# STM32F103VE.net
KiCad netlist of a schematic drawn in Altium Designer
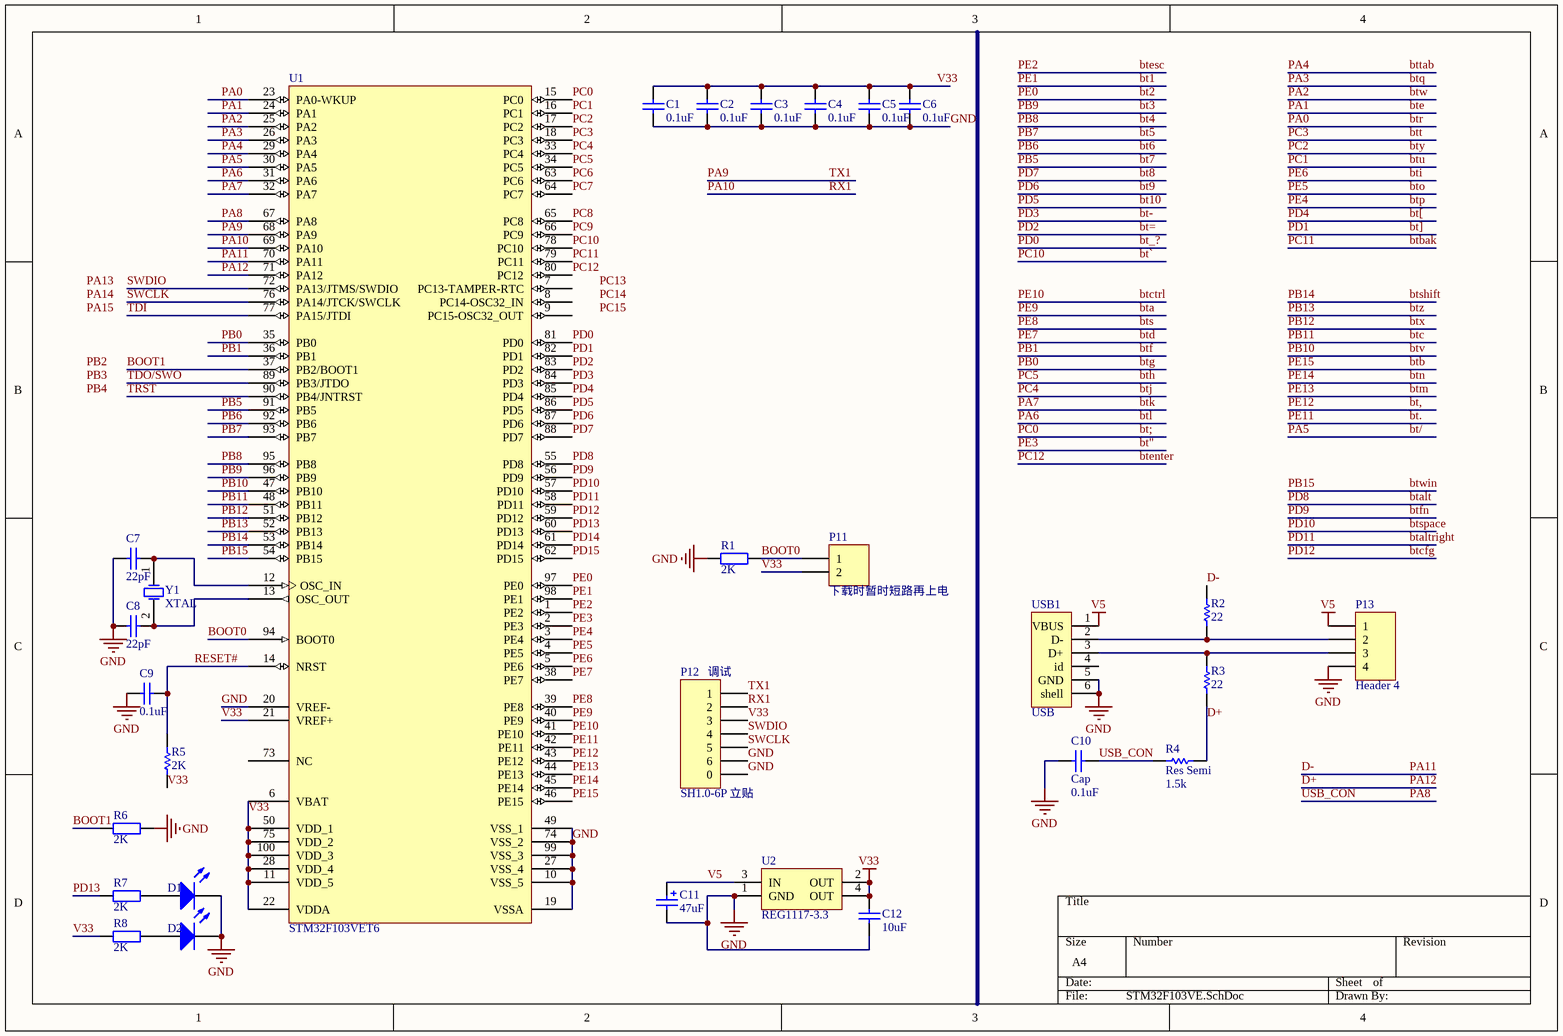
[diagram p0: STM32F103VE.SchDoc]

(export (version "E")
  (design (tool "Eeschema 10.0.6"))
  (components
    (comp (ref "C1")
      (value "0.1uF")
      (footprint "CAP0805(2512)")
      (description "Capacitor")
      (fields (field (name "Comment") "Cap") (field (name "PUBLISHER") "Altium Limited"))
      (libsource (lib "Miscellaneous Devices") (part "Cap"))
    )
    (comp (ref "C2")
      (value "0.1uF")
      (footprint "CAP0805(2512)")
      (description "Capacitor")
      (fields (field (name "Comment") "Cap") (field (name "PUBLISHER") "Altium Limited"))
      (libsource (lib "Miscellaneous Devices") (part "Cap"))
    )
    (comp (ref "C3")
      (value "0.1uF")
      (footprint "CAP0805(2512)")
      (description "Capacitor")
      (fields (field (name "Comment") "Cap") (field (name "PUBLISHER") "Altium Limited"))
      (libsource (lib "Miscellaneous Devices") (part "Cap"))
    )
    (comp (ref "C4")
      (value "0.1uF")
      (footprint "CAP0805(2512)")
      (description "Capacitor")
      (fields (field (name "Comment") "Cap") (field (name "PUBLISHER") "Altium Limited"))
      (libsource (lib "Miscellaneous Devices") (part "Cap"))
    )
    (comp (ref "C5")
      (value "0.1uF")
      (footprint "CAP0805(2512)")
      (description "Capacitor")
      (fields (field (name "Comment") "Cap") (field (name "PUBLISHER") "Altium Limited"))
      (libsource (lib "Miscellaneous Devices") (part "Cap"))
    )
    (comp (ref "C6")
      (value "0.1uF")
      (footprint "CAP0805(2512)")
      (description "Capacitor")
      (fields (field (name "Comment") "Cap") (field (name "PUBLISHER") "Altium Limited"))
      (libsource (lib "Miscellaneous Devices") (part "Cap"))
    )
    (comp (ref "C7")
      (value "22pF")
      (footprint "CAP0805(2512)")
      (description "Capacitor")
      (fields (field (name "Comment") "Cap") (field (name "PUBLISHER") "Altium Limited"))
      (libsource (lib "Miscellaneous Devices") (part "Cap"))
    )
    (comp (ref "C8")
      (value "22pF")
      (footprint "CAP0805(2512)")
      (description "Capacitor")
      (fields (field (name "Comment") "Cap") (field (name "PUBLISHER") "Altium Limited"))
      (libsource (lib "Miscellaneous Devices") (part "Cap"))
    )
    (comp (ref "C9")
      (value "0.1uF")
      (footprint "CAP0805(2512)")
      (description "Capacitor")
      (fields (field (name "Comment") "Cap") (field (name "PUBLISHER") "Altium Limited"))
      (libsource (lib "Miscellaneous Devices") (part "Cap"))
    )
    (comp (ref "C10")
      (value "Cap")
      (footprint "CAP0805(2512)")
      (description "Capacitor")
      (fields (field (name "ALTIUM_VALUE") "0.1uF") (field (name "PUBLISHER") "Altium Limited"))
      (libsource (lib "Miscellaneous Devices") (part "Cap"))
    )
    (comp (ref "C11")
      (value "47uF")
      (footprint "CAP0805(2512)")
      (description "Polarized Capacitor (Axial)")
      (fields (field (name "Comment") "Cap Pol2") (field (name "PUBLISHER") "Altium Limited"))
      (libsource (lib "Miscellaneous Devices") (part "Cap Pol2"))
    )
    (comp (ref "C12")
      (value "10uF")
      (footprint "CAP0805(2512)")
      (description "Capacitor")
      (fields (field (name "Comment") "Cap") (field (name "PUBLISHER") "Altium Limited"))
      (libsource (lib "Miscellaneous Devices") (part "Cap"))
    )
    (comp (ref "D1")
      (value "LED0")
      (footprint "DIODE_100mil")
      (description "Typical INFRARED GaAs LED")
      (fields (field (name "PUBLISHER") "Altium Limited"))
      (libsource (lib "Miscellaneous Devices") (part "LED0"))
    )
    (comp (ref "D2")
      (value "LED0")
      (footprint "DIODE_100mil")
      (description "Typical INFRARED GaAs LED")
      (fields (field (name "PUBLISHER") "Altium Limited"))
      (libsource (lib "Miscellaneous Devices") (part "LED0"))
    )
    (comp (ref "P11")
      (value "下载时暂时短路再上电")
      (footprint "HDR1X2")
      (description "Header, 2-Pin")
      (fields (field (name "PUBLISHER") "Altium Limited"))
      (libsource (lib "Miscellaneous Connectors") (part "Header 2"))
    )
    (comp (ref "P12")
      (value "SH1.0-6P 立贴")
      (footprint "SH1.0-6P立")
      (description "Header, 7-Pin")
      (fields (field (name "PUBLISHER") "Altium Limited"))
      (libsource (lib "Miscellaneous Connectors") (part "Header 7"))
    )
    (comp (ref "P13")
      (value "Header 4")
      (footprint "HDR1X4")
      (description "Header, 4-Pin")
      (fields (field (name "PUBLISHER") "Altium Limited"))
      (libsource (lib "Miscellaneous Connectors") (part "Header 4"))
    )
    (comp (ref "R1")
      (value "2K")
      (footprint "RES0805(2012M)")
      (description "Resistor")
      (fields (field (name "Comment") "Res2") (field (name "PUBLISHER") "Altium Limited"))
      (libsource (lib "Miscellaneous Devices") (part "Res2"))
    )
    (comp (ref "R2")
      (value "22")
      (footprint "RES0805(2012M)")
      (description "Semiconductor Resistor")
      (fields (field (name "Comment") "Res Semi") (field (name "PUBLISHER") "Altium Limited"))
      (libsource (lib "Miscellaneous Devices") (part "Res Semi"))
    )
    (comp (ref "R3")
      (value "22")
      (footprint "RES0805(2012M)")
      (description "Semiconductor Resistor")
      (fields (field (name "Comment") "Res Semi") (field (name "PUBLISHER") "Altium Limited"))
      (libsource (lib "Miscellaneous Devices") (part "Res Semi"))
    )
    (comp (ref "R4")
      (value "Res Semi")
      (footprint "RES0805(2012M)")
      (description "Semiconductor Resistor")
      (fields (field (name "ALTIUM_VALUE") "1.5k") (field (name "PUBLISHER") "Altium Limited"))
      (libsource (lib "Miscellaneous Devices") (part "Res Semi"))
    )
    (comp (ref "R5")
      (value "2K")
      (footprint "RES0805(2012M)")
      (description "Semiconductor Resistor")
      (fields (field (name "Comment") "Res Semi") (field (name "PUBLISHER") "Altium Limited"))
      (libsource (lib "Miscellaneous Devices") (part "Res Semi"))
    )
    (comp (ref "R6")
      (value "2K")
      (footprint "RES0805(2012M)")
      (description "Resistor")
      (fields (field (name "Comment") "Res2") (field (name "PUBLISHER") "Altium Limited"))
      (libsource (lib "Miscellaneous Devices") (part "Res2"))
    )
    (comp (ref "R7")
      (value "2K")
      (footprint "RES0805(2012M)")
      (description "Resistor")
      (fields (field (name "Comment") "Res2") (field (name "PUBLISHER") "Altium Limited"))
      (libsource (lib "") (part "Res2_1"))
    )
    (comp (ref "R8")
      (value "2K")
      (footprint "RES0805(2012M)")
      (description "Resistor")
      (fields (field (name "Comment") "Res2") (field (name "PUBLISHER") "Altium Limited"))
      (libsource (lib "") (part "Res2_1"))
    )
    (comp (ref "U1")
      (value "STM32F103VET6")
      (footprint "LQFP-100")
      (description "STM32 ARM-based 32-bit MCU with 64 Kbytes Flash, 100-pin LQFP, Industrial Temperature")
      (fields (field (name "PUBLISHER") "Altium Limited"))
      (libsource (lib "ST Microcontroller 32-Bit STM32") (part "STM32F103VBT6"))
    )
    (comp (ref "U2")
      (value "REG1117-3.3")
      (footprint "ZZ311")
      (description "800mA and 1A Low Dropout Positive Regulator 2.85V, 3.3V, 5V, and Adjustable")
      (fields (field (name "PUBLISHER") "Altium Limited"))
      (libsource (lib "power") (part "REG1117-3.3"))
    )
    (comp (ref "USB1") (value "USB") (footprint "MICRO-USB") (libsource (lib "*") (part "USB")))
    (comp (ref "Y1")
      (value "XTAL")
      (footprint "XTAL_0.4")
      (description "Crystal Oscillator")
      (fields (field (name "PUBLISHER") "Altium Limited"))
      (libsource (lib "Miscellaneous Devices") (part "XTAL"))
    )
  )
  (nets
    (net (code "1") (name "/BOOT0") (class "Default")
      (node (ref "P11") (pin "1") (pinfunction "1_1") (pintype "passive"))
      (node (ref "R1") (pin "1") (pinfunction "1_1") (pintype "passive"))
      (node (ref "U1") (pin "94") (pinfunction "BOOT0_94") (pintype "input"))
    )
    (net (code "2") (name "/BOOT1") (class "Default")
      (node (ref "R6") (pin "2") (pinfunction "2_2") (pintype "passive"))
      (node (ref "U1") (pin "37") (pinfunction "PB2/BOOT1_37") (pintype "bidirectional"))
    )
    (net (code "3") (name "/D+") (class "Default")
      (node (ref "R3") (pin "2") (pinfunction "2_2") (pintype "passive"))
      (node (ref "R4") (pin "2") (pinfunction "2_2") (pintype "passive"))
      (node (ref "U1") (pin "71") (pinfunction "PA12_71") (pintype "bidirectional"))
    )
    (net (code "4") (name "/D-") (class "Default")
      (node (ref "R2") (pin "2") (pinfunction "2_2") (pintype "passive"))
      (node (ref "U1") (pin "70") (pinfunction "PA11_70") (pintype "bidirectional"))
    )
    (net (code "5") (name "/PA0") (class "Default")
      (node (ref "U1") (pin "23") (pinfunction "PA0-WKUP_23") (pintype "bidirectional"))
    )
    (net (code "6") (name "/PA1") (class "Default")
      (node (ref "U1") (pin "24") (pinfunction "PA1_24") (pintype "bidirectional"))
    )
    (net (code "7") (name "/PA2") (class "Default")
      (node (ref "U1") (pin "25") (pinfunction "PA2_25") (pintype "bidirectional"))
    )
    (net (code "8") (name "/PA3") (class "Default")
      (node (ref "U1") (pin "26") (pinfunction "PA3_26") (pintype "bidirectional"))
    )
    (net (code "9") (name "/PA4") (class "Default")
      (node (ref "U1") (pin "29") (pinfunction "PA4_29") (pintype "bidirectional"))
    )
    (net (code "10") (name "/PA5") (class "Default")
      (node (ref "U1") (pin "30") (pinfunction "PA5_30") (pintype "bidirectional"))
    )
    (net (code "11") (name "/PA6") (class "Default")
      (node (ref "U1") (pin "31") (pinfunction "PA6_31") (pintype "bidirectional"))
    )
    (net (code "12") (name "/PA7") (class "Default")
      (node (ref "U1") (pin "32") (pinfunction "PA7_32") (pintype "bidirectional"))
    )
    (net (code "13") (name "/PA8") (class "Default")
      (node (ref "C10") (pin "1") (pinfunction "1_1") (pintype "passive"))
      (node (ref "R4") (pin "1") (pinfunction "1_1") (pintype "passive"))
      (node (ref "U1") (pin "67") (pinfunction "PA8_67") (pintype "bidirectional"))
    )
    (net (code "14") (name "/PA9") (class "Default")
      (node (ref "P12") (pin "1") (pinfunction "1_1") (pintype "passive"))
      (node (ref "U1") (pin "68") (pinfunction "PA9_68") (pintype "bidirectional"))
    )
    (net (code "15") (name "/PA10") (class "Default")
      (node (ref "P12") (pin "2") (pinfunction "2_2") (pintype "passive"))
      (node (ref "U1") (pin "69") (pinfunction "PA10_69") (pintype "bidirectional"))
    )
    (net (code "19") (name "/PB0") (class "Default")
      (node (ref "U1") (pin "35") (pinfunction "PB0_35") (pintype "bidirectional"))
    )
    (net (code "20") (name "/PB1") (class "Default")
      (node (ref "U1") (pin "36") (pinfunction "PB1_36") (pintype "bidirectional"))
    )
    (net (code "24") (name "/PB5") (class "Default")
      (node (ref "U1") (pin "91") (pinfunction "PB5_91") (pintype "bidirectional"))
    )
    (net (code "25") (name "/PB6") (class "Default")
      (node (ref "U1") (pin "92") (pinfunction "PB6_92") (pintype "bidirectional"))
    )
    (net (code "26") (name "/PB7") (class "Default")
      (node (ref "U1") (pin "93") (pinfunction "PB7_93") (pintype "bidirectional"))
    )
    (net (code "27") (name "/PB8") (class "Default")
      (node (ref "U1") (pin "95") (pinfunction "PB8_95") (pintype "bidirectional"))
    )
    (net (code "28") (name "/PB9") (class "Default")
      (node (ref "U1") (pin "96") (pinfunction "PB9_96") (pintype "bidirectional"))
    )
    (net (code "29") (name "/PB10") (class "Default")
      (node (ref "U1") (pin "47") (pinfunction "PB10_47") (pintype "bidirectional"))
    )
    (net (code "30") (name "/PB11") (class "Default")
      (node (ref "U1") (pin "48") (pinfunction "PB11_48") (pintype "bidirectional"))
    )
    (net (code "31") (name "/PB12") (class "Default")
      (node (ref "U1") (pin "51") (pinfunction "PB12_51") (pintype "bidirectional"))
    )
    (net (code "32") (name "/PB13") (class "Default")
      (node (ref "U1") (pin "52") (pinfunction "PB13_52") (pintype "bidirectional"))
    )
    (net (code "33") (name "/PB14") (class "Default")
      (node (ref "U1") (pin "53") (pinfunction "PB14_53") (pintype "bidirectional"))
    )
    (net (code "34") (name "/PB15") (class "Default")
      (node (ref "U1") (pin "54") (pinfunction "PB15_54") (pintype "bidirectional"))
    )
    (net (code "35") (name "/PC0") (class "Default")
      (node (ref "U1") (pin "15") (pinfunction "PC0_15") (pintype "bidirectional"))
    )
    (net (code "36") (name "/PC1") (class "Default")
      (node (ref "U1") (pin "16") (pinfunction "PC1_16") (pintype "bidirectional"))
    )
    (net (code "37") (name "/PC2") (class "Default")
      (node (ref "U1") (pin "17") (pinfunction "PC2_17") (pintype "bidirectional"))
    )
    (net (code "38") (name "/PC3") (class "Default")
      (node (ref "U1") (pin "18") (pinfunction "PC3_18") (pintype "bidirectional"))
    )
    (net (code "39") (name "/PC4") (class "Default")
      (node (ref "U1") (pin "33") (pinfunction "PC4_33") (pintype "bidirectional"))
    )
    (net (code "40") (name "/PC5") (class "Default")
      (node (ref "U1") (pin "34") (pinfunction "PC5_34") (pintype "bidirectional"))
    )
    (net (code "41") (name "/PC6") (class "Default")
      (node (ref "U1") (pin "63") (pinfunction "PC6_63") (pintype "bidirectional"))
    )
    (net (code "42") (name "/PC7") (class "Default")
      (node (ref "U1") (pin "64") (pinfunction "PC7_64") (pintype "bidirectional"))
    )
    (net (code "43") (name "/PC8") (class "Default")
      (node (ref "U1") (pin "65") (pinfunction "PC8_65") (pintype "bidirectional"))
    )
    (net (code "44") (name "/PC9") (class "Default")
      (node (ref "U1") (pin "66") (pinfunction "PC9_66") (pintype "bidirectional"))
    )
    (net (code "45") (name "/PC10") (class "Default")
      (node (ref "U1") (pin "78") (pinfunction "PC10_78") (pintype "bidirectional"))
    )
    (net (code "46") (name "/PC11") (class "Default")
      (node (ref "U1") (pin "79") (pinfunction "PC11_79") (pintype "bidirectional"))
    )
    (net (code "47") (name "/PC12") (class "Default")
      (node (ref "U1") (pin "80") (pinfunction "PC12_80") (pintype "bidirectional"))
    )
    (net (code "51") (name "/PD0") (class "Default")
      (node (ref "U1") (pin "81") (pinfunction "PD0_81") (pintype "bidirectional"))
    )
    (net (code "52") (name "/PD1") (class "Default")
      (node (ref "U1") (pin "82") (pinfunction "PD1_82") (pintype "bidirectional"))
    )
    (net (code "53") (name "/PD2") (class "Default")
      (node (ref "U1") (pin "83") (pinfunction "PD2_83") (pintype "bidirectional"))
    )
    (net (code "54") (name "/PD3") (class "Default")
      (node (ref "U1") (pin "84") (pinfunction "PD3_84") (pintype "bidirectional"))
    )
    (net (code "55") (name "/PD4") (class "Default")
      (node (ref "U1") (pin "85") (pinfunction "PD4_85") (pintype "bidirectional"))
    )
    (net (code "56") (name "/PD5") (class "Default")
      (node (ref "U1") (pin "86") (pinfunction "PD5_86") (pintype "bidirectional"))
    )
    (net (code "57") (name "/PD6") (class "Default")
      (node (ref "U1") (pin "87") (pinfunction "PD6_87") (pintype "bidirectional"))
    )
    (net (code "58") (name "/PD7") (class "Default")
      (node (ref "U1") (pin "88") (pinfunction "PD7_88") (pintype "bidirectional"))
    )
    (net (code "59") (name "/PD8") (class "Default")
      (node (ref "U1") (pin "55") (pinfunction "PD8_55") (pintype "bidirectional"))
    )
    (net (code "60") (name "/PD9") (class "Default")
      (node (ref "U1") (pin "56") (pinfunction "PD9_56") (pintype "bidirectional"))
    )
    (net (code "61") (name "/PD10") (class "Default")
      (node (ref "U1") (pin "57") (pinfunction "PD10_57") (pintype "bidirectional"))
    )
    (net (code "62") (name "/PD11") (class "Default")
      (node (ref "U1") (pin "58") (pinfunction "PD11_58") (pintype "bidirectional"))
    )
    (net (code "63") (name "/PD12") (class "Default")
      (node (ref "U1") (pin "59") (pinfunction "PD12_59") (pintype "bidirectional"))
    )
    (net (code "64") (name "/PD13") (class "Default")
      (node (ref "R7") (pin "1") (pinfunction "1_1") (pintype "passive"))
      (node (ref "U1") (pin "60") (pinfunction "PD13_60") (pintype "bidirectional"))
    )
    (net (code "65") (name "/PD14") (class "Default")
      (node (ref "U1") (pin "61") (pinfunction "PD14_61") (pintype "bidirectional"))
    )
    (net (code "66") (name "/PD15") (class "Default")
      (node (ref "U1") (pin "62") (pinfunction "PD15_62") (pintype "bidirectional"))
    )
    (net (code "67") (name "/PE0") (class "Default")
      (node (ref "U1") (pin "97") (pinfunction "PE0_97") (pintype "bidirectional"))
    )
    (net (code "68") (name "/PE1") (class "Default")
      (node (ref "U1") (pin "98") (pinfunction "PE1_98") (pintype "bidirectional"))
    )
    (net (code "69") (name "/PE2") (class "Default")
      (node (ref "U1") (pin "1") (pinfunction "PE2_1") (pintype "bidirectional"))
    )
    (net (code "70") (name "/PE3") (class "Default")
      (node (ref "U1") (pin "2") (pinfunction "PE3_2") (pintype "bidirectional"))
    )
    (net (code "71") (name "/PE4") (class "Default")
      (node (ref "U1") (pin "3") (pinfunction "PE4_3") (pintype "bidirectional"))
    )
    (net (code "72") (name "/PE5") (class "Default")
      (node (ref "U1") (pin "4") (pinfunction "PE5_4") (pintype "bidirectional"))
    )
    (net (code "73") (name "/PE6") (class "Default")
      (node (ref "U1") (pin "5") (pinfunction "PE6_5") (pintype "bidirectional"))
    )
    (net (code "74") (name "/PE7") (class "Default")
      (node (ref "U1") (pin "38") (pinfunction "PE7_38") (pintype "bidirectional"))
    )
    (net (code "75") (name "/PE8") (class "Default")
      (node (ref "U1") (pin "39") (pinfunction "PE8_39") (pintype "bidirectional"))
    )
    (net (code "76") (name "/PE9") (class "Default")
      (node (ref "U1") (pin "40") (pinfunction "PE9_40") (pintype "bidirectional"))
    )
    (net (code "77") (name "/PE10") (class "Default")
      (node (ref "U1") (pin "41") (pinfunction "PE10_41") (pintype "bidirectional"))
    )
    (net (code "78") (name "/PE11") (class "Default")
      (node (ref "U1") (pin "42") (pinfunction "PE11_42") (pintype "bidirectional"))
    )
    (net (code "79") (name "/PE12") (class "Default")
      (node (ref "U1") (pin "43") (pinfunction "PE12_43") (pintype "bidirectional"))
    )
    (net (code "80") (name "/PE13") (class "Default")
      (node (ref "U1") (pin "44") (pinfunction "PE13_44") (pintype "bidirectional"))
    )
    (net (code "81") (name "/PE14") (class "Default")
      (node (ref "U1") (pin "45") (pinfunction "PE14_45") (pintype "bidirectional"))
    )
    (net (code "82") (name "/PE15") (class "Default")
      (node (ref "U1") (pin "46") (pinfunction "PE15_46") (pintype "bidirectional"))
    )
    (net (code "83") (name "/RESET#") (class "Default")
      (node (ref "C9") (pin "1") (pinfunction "1_1") (pintype "passive"))
      (node (ref "R5") (pin "2") (pinfunction "2_2") (pintype "passive"))
      (node (ref "U1") (pin "14") (pinfunction "NRST_14") (pintype "bidirectional"))
    )
    (net (code "84") (name "/SWCLK") (class "Default")
      (node (ref "P12") (pin "5") (pinfunction "5_5") (pintype "passive"))
      (node (ref "U1") (pin "76") (pinfunction "PA14/JTCK/SWCLK_76") (pintype "bidirectional"))
    )
    (net (code "85") (name "/SWDIO") (class "Default")
      (node (ref "P12") (pin "4") (pinfunction "4_4") (pintype "passive"))
      (node (ref "U1") (pin "72") (pinfunction "PA13/JTMS/SWDIO_72") (pintype "bidirectional"))
    )
    (net (code "86") (name "/TDI") (class "Default")
      (node (ref "U1") (pin "77") (pinfunction "PA15/JTDI_77") (pintype "bidirectional"))
    )
    (net (code "87") (name "/TDO{slash}SWO") (class "Default")
      (node (ref "U1") (pin "89") (pinfunction "PB3/JTDO_89") (pintype "bidirectional"))
    )
    (net (code "88") (name "/TRST") (class "Default")
      (node (ref "U1") (pin "90") (pinfunction "PB4/JNTRST_90") (pintype "bidirectional"))
    )
    (net (code "89") (name "GND") (class "Default")
      (node (ref "C1") (pin "1") (pinfunction "1_1") (pintype "passive"))
      (node (ref "C10") (pin "2") (pinfunction "2_2") (pintype "passive"))
      (node (ref "C11") (pin "2") (pinfunction "2_2") (pintype "passive"))
      (node (ref "C12") (pin "1") (pinfunction "1_1") (pintype "passive"))
      (node (ref "C2") (pin "1") (pinfunction "1_1") (pintype "passive"))
      (node (ref "C3") (pin "1") (pinfunction "1_1") (pintype "passive"))
      (node (ref "C4") (pin "1") (pinfunction "1_1") (pintype "passive"))
      (node (ref "C5") (pin "1") (pinfunction "1_1") (pintype "passive"))
      (node (ref "C6") (pin "1") (pinfunction "1_1") (pintype "passive"))
      (node (ref "C7") (pin "1") (pinfunction "1_1") (pintype "passive"))
      (node (ref "C8") (pin "1") (pinfunction "1_1") (pintype "passive"))
      (node (ref "C9") (pin "2") (pinfunction "2_2") (pintype "passive"))
      (node (ref "D1") (pin "2") (pinfunction "K_2") (pintype "passive"))
      (node (ref "D2") (pin "2") (pinfunction "K_2") (pintype "passive"))
      (node (ref "P12") (pin "0") (pinfunction "0_0") (pintype "passive"))
      (node (ref "P12") (pin "6") (pinfunction "6_6") (pintype "passive"))
      (node (ref "P13") (pin "4") (pinfunction "4_4") (pintype "passive"))
      (node (ref "R1") (pin "2") (pinfunction "2_2") (pintype "passive"))
      (node (ref "R6") (pin "1") (pinfunction "1_1") (pintype "passive"))
      (node (ref "U1") (pin "10") (pinfunction "VSS_5_10") (pintype "power_in"))
      (node (ref "U1") (pin "19") (pinfunction "VSSA_19") (pintype "power_in"))
      (node (ref "U1") (pin "20") (pinfunction "VREF-_20") (pintype "power_in"))
      (node (ref "U1") (pin "27") (pinfunction "VSS_4_27") (pintype "power_in"))
      (node (ref "U1") (pin "49") (pinfunction "VSS_1_49") (pintype "power_in"))
      (node (ref "U1") (pin "74") (pinfunction "VSS_2_74") (pintype "power_in"))
      (node (ref "U1") (pin "99") (pinfunction "VSS_3_99") (pintype "power_in"))
      (node (ref "U2") (pin "1") (pinfunction "GND_1") (pintype "power_in"))
      (node (ref "USB1") (pin "5") (pinfunction "GND_5") (pintype "passive"))
      (node (ref "USB1") (pin "6") (pinfunction "shell_6") (pintype "passive"))
    )
    (net (code "90") (name "Net-(D1-A)") (class "Default")
      (node (ref "D1") (pin "1") (pinfunction "A_1") (pintype "passive"))
      (node (ref "R7") (pin "2") (pinfunction "2_2") (pintype "passive"))
    )
    (net (code "91") (name "Net-(D2-A)") (class "Default")
      (node (ref "D2") (pin "1") (pinfunction "A_1") (pintype "passive"))
      (node (ref "R8") (pin "2") (pinfunction "2_2") (pintype "passive"))
    )
    (net (code "92") (name "Net-(U1-OSC_IN)") (class "Default")
      (node (ref "C7") (pin "2") (pinfunction "2_2") (pintype "passive"))
      (node (ref "U1") (pin "12") (pinfunction "OSC_IN_12") (pintype "input"))
      (node (ref "Y1") (pin "1") (pinfunction "OSC1_1") (pintype "passive"))
    )
    (net (code "93") (name "Net-(U1-OSC_OUT)") (class "Default")
      (node (ref "C8") (pin "2") (pinfunction "2_2") (pintype "passive"))
      (node (ref "U1") (pin "13") (pinfunction "OSC_OUT_13") (pintype "output"))
      (node (ref "Y1") (pin "2") (pinfunction "OSC2_2") (pintype "passive"))
    )
    (net (code "94") (name "Net-(USB1-D+)") (class "Default")
      (node (ref "P13") (pin "3") (pinfunction "3_3") (pintype "passive"))
      (node (ref "R3") (pin "1") (pinfunction "1_1") (pintype "passive"))
      (node (ref "USB1") (pin "3") (pinfunction "D+_3") (pintype "passive"))
    )
    (net (code "95") (name "Net-(USB1-D-)") (class "Default")
      (node (ref "P13") (pin "2") (pinfunction "2_2") (pintype "passive"))
      (node (ref "R2") (pin "1") (pinfunction "1_1") (pintype "passive"))
      (node (ref "USB1") (pin "2") (pinfunction "D-_2") (pintype "passive"))
    )
    (net (code "96") (name "V5") (class "Default")
      (node (ref "C11") (pin "1") (pinfunction "1_1") (pintype "passive"))
      (node (ref "P13") (pin "1") (pinfunction "1_1") (pintype "passive"))
      (node (ref "U2") (pin "3") (pinfunction "IN_3") (pintype "power_in"))
      (node (ref "USB1") (pin "1") (pinfunction "VBUS_1") (pintype "passive"))
    )
    (net (code "97") (name "V33") (class "Default")
      (node (ref "C1") (pin "2") (pinfunction "2_2") (pintype "passive"))
      (node (ref "C12") (pin "2") (pinfunction "2_2") (pintype "passive"))
      (node (ref "C2") (pin "2") (pinfunction "2_2") (pintype "passive"))
      (node (ref "C3") (pin "2") (pinfunction "2_2") (pintype "passive"))
      (node (ref "C4") (pin "2") (pinfunction "2_2") (pintype "passive"))
      (node (ref "C5") (pin "2") (pinfunction "2_2") (pintype "passive"))
      (node (ref "C6") (pin "2") (pinfunction "2_2") (pintype "passive"))
      (node (ref "P11") (pin "2") (pinfunction "2_2") (pintype "passive"))
      (node (ref "P12") (pin "3") (pinfunction "3_3") (pintype "passive"))
      (node (ref "R5") (pin "1") (pinfunction "1_1") (pintype "passive"))
      (node (ref "R8") (pin "1") (pinfunction "1_1") (pintype "passive"))
      (node (ref "U1") (pin "100") (pinfunction "VDD_3_100") (pintype "power_in"))
      (node (ref "U1") (pin "11") (pinfunction "VDD_5_11") (pintype "power_in"))
      (node (ref "U1") (pin "21") (pinfunction "VREF+_21") (pintype "power_in"))
      (node (ref "U1") (pin "22") (pinfunction "VDDA_22") (pintype "power_in"))
      (node (ref "U1") (pin "28") (pinfunction "VDD_4_28") (pintype "power_in"))
      (node (ref "U1") (pin "50") (pinfunction "VDD_1_50") (pintype "power_in"))
      (node (ref "U1") (pin "6") (pinfunction "VBAT_6") (pintype "power_in"))
      (node (ref "U1") (pin "75") (pinfunction "VDD_2_75") (pintype "power_in"))
      (node (ref "U2") (pin "2") (pinfunction "OUT_2") (pintype "power_in"))
      (node (ref "U2") (pin "4") (pinfunction "OUT_4") (pintype "power_in"))
    )
    (net (code "98") (name "unconnected-(U1-NC-Pad73)") (class "Default")
      (node (ref "U1") (pin "73") (pinfunction "NC_73") (pintype "passive"))
    )
    (net (code "99") (name "unconnected-(U1-PC13-TAMPER-RTC-Pad7)") (class "Default")
      (node (ref "U1") (pin "7") (pinfunction "PC13-TAMPER-RTC_7") (pintype "bidirectional"))
    )
    (net (code "100") (name "unconnected-(U1-PC14-OSC32_IN-Pad8)") (class "Default")
      (node (ref "U1") (pin "8") (pinfunction "PC14-OSC32_IN_8") (pintype "bidirectional"))
    )
    (net (code "101") (name "unconnected-(U1-PC15-OSC32_OUT-Pad9)") (class "Default")
      (node (ref "U1") (pin "9") (pinfunction "PC15-OSC32_OUT_9") (pintype "bidirectional"))
    )
    (net (code "102") (name "unconnected-(USB1-id-Pad4)") (class "Default")
      (node (ref "USB1") (pin "4") (pinfunction "id_4") (pintype "passive"))
    )
  )
)
